# IMX8_INTERFACE.net
KiCad netlist of a schematic drawn in Altium Designer
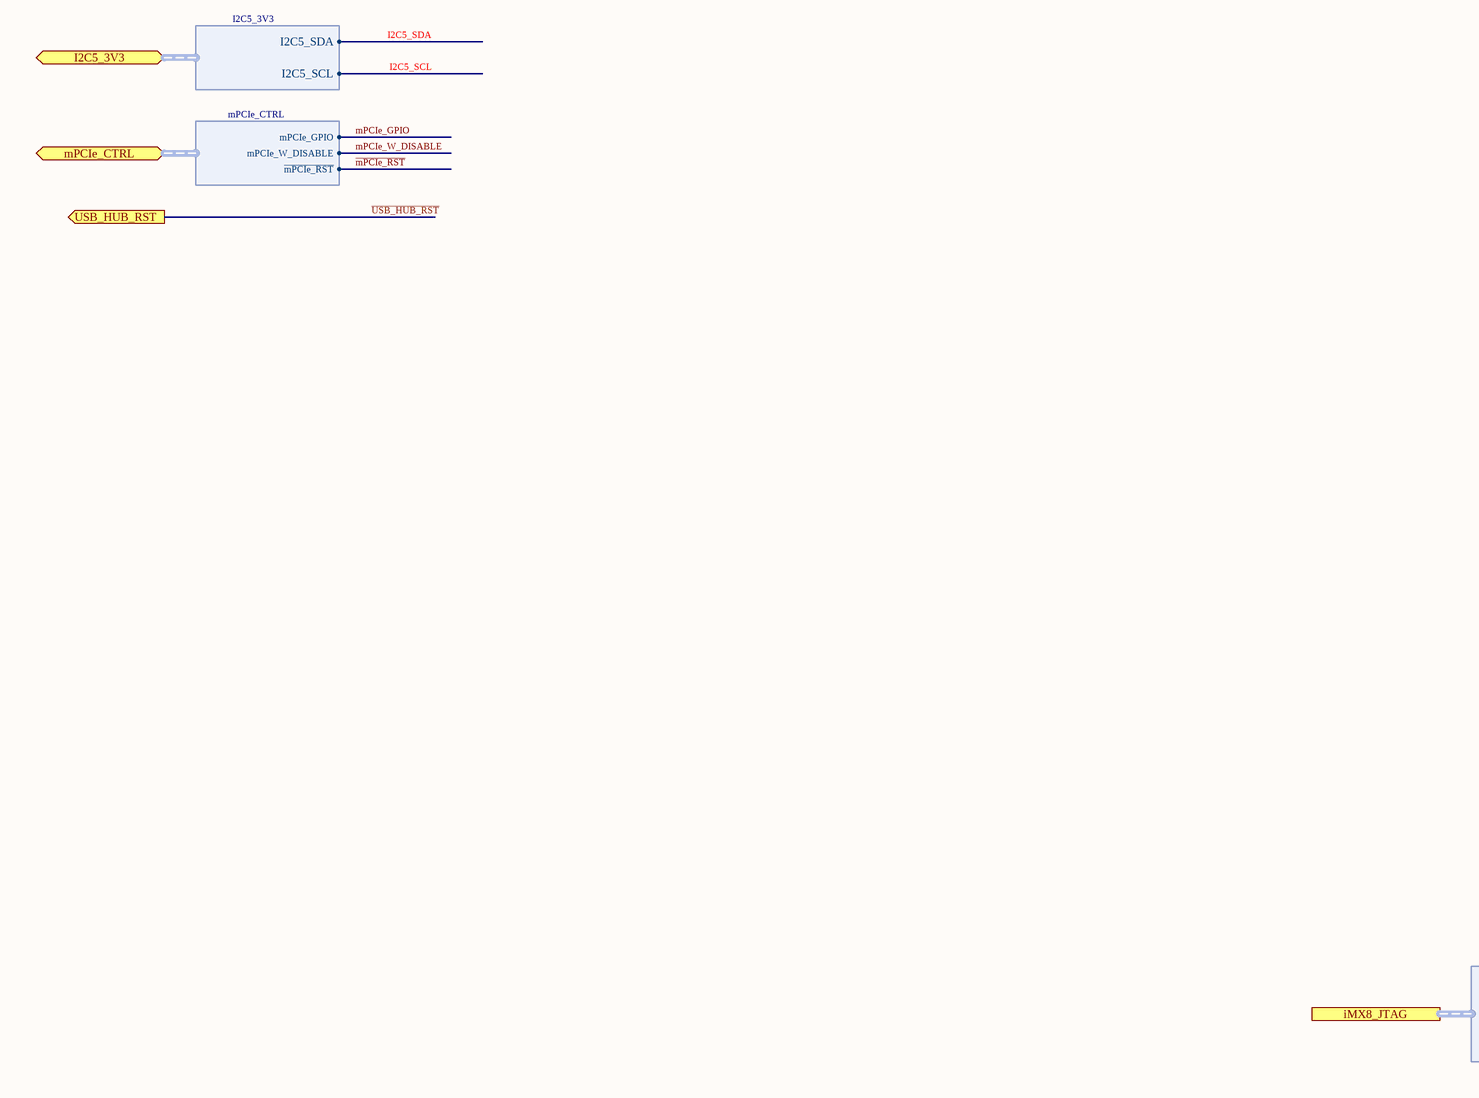
[diagram p0: IMX8_INTERFACE.SchDoc, bottom left]
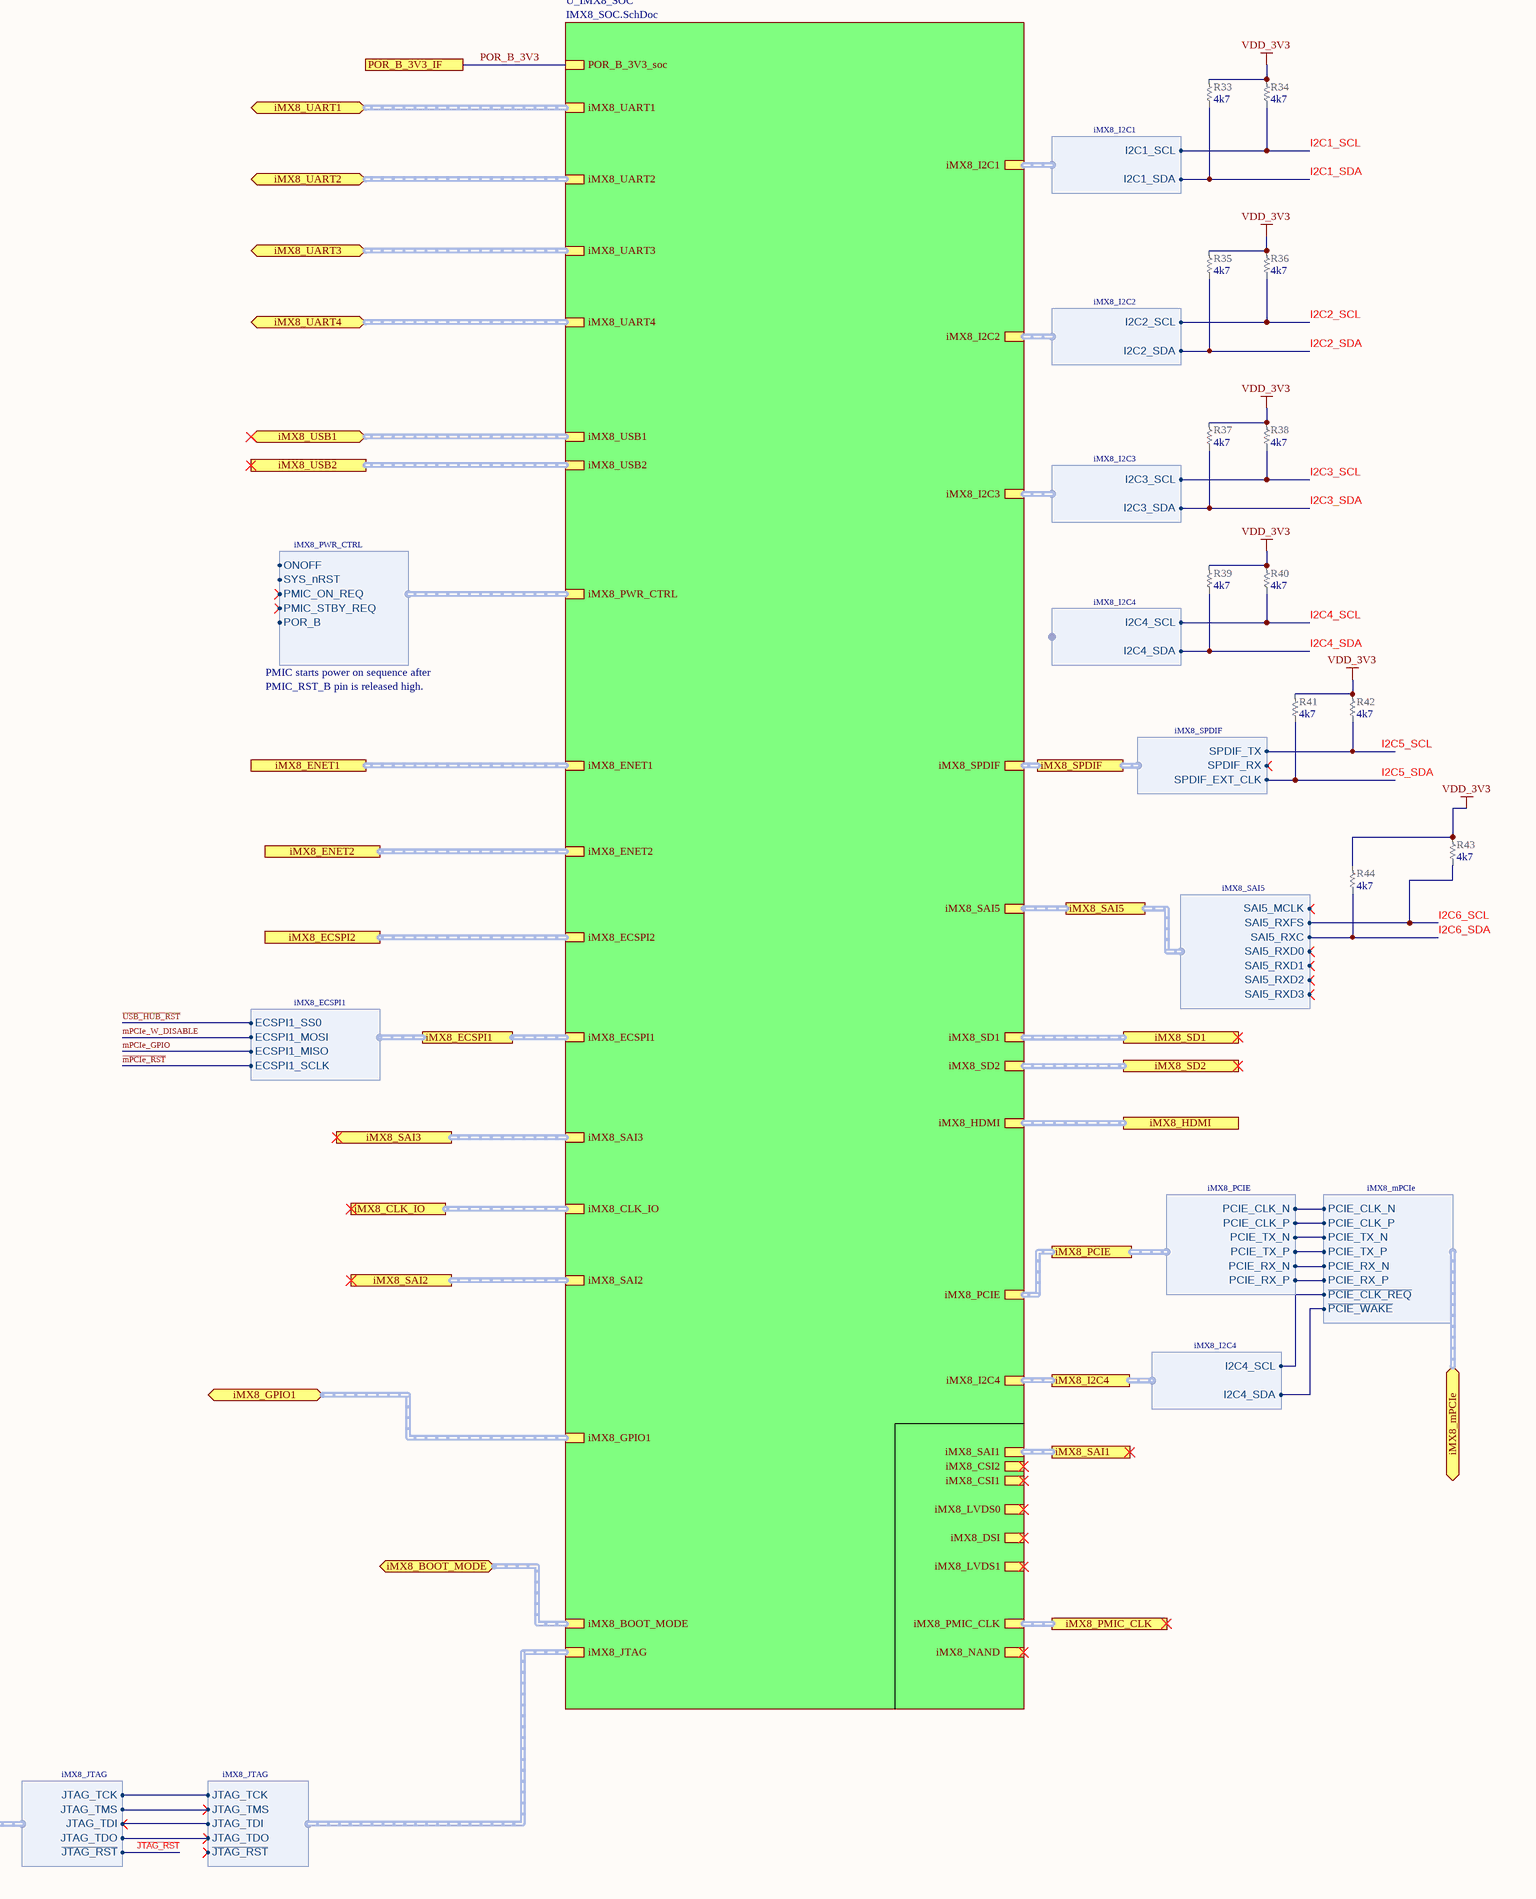
[diagram p1: IMX8_INTERFACE.SchDoc, bottom right]

(export (version "E")
  (design (tool "Eeschema 10.0.6"))
  (components
    (comp (ref "R33")
      (value "4k7")
      (footprint "RES_0201_UN1Q")
      (description "RES")
      (fields (field (name "PART NUMBER") "RC0201FR-074K7L") (field (name "MANUFACTURER") "Yageo Group"))
      (libsource (lib "CM5_library") (part "CMP-001-000475-13"))
    )
    (comp (ref "R34")
      (value "4k7")
      (footprint "RES_0201_UN1Q")
      (description "RES")
      (fields (field (name "PART NUMBER") "RC0201FR-074K7L") (field (name "MANUFACTURER") "Yageo Group"))
      (libsource (lib "CM5_library") (part "CMP-001-000475-13"))
    )
    (comp (ref "R35")
      (value "4k7")
      (footprint "RES_0201_UN1Q")
      (description "RES")
      (fields (field (name "PART NUMBER") "RC0201FR-074K7L") (field (name "MANUFACTURER") "Yageo Group"))
      (libsource (lib "CM5_library") (part "CMP-001-000475-13"))
    )
    (comp (ref "R36")
      (value "4k7")
      (footprint "RES_0201_UN1Q")
      (description "RES")
      (fields (field (name "PART NUMBER") "RC0201FR-074K7L") (field (name "MANUFACTURER") "Yageo Group"))
      (libsource (lib "CM5_library") (part "CMP-001-000475-13"))
    )
    (comp (ref "R37")
      (value "4k7")
      (footprint "RES_0201_UN1Q")
      (description "RES")
      (fields (field (name "PART NUMBER") "RC0201FR-074K7L") (field (name "MANUFACTURER") "Yageo Group"))
      (libsource (lib "CM5_library") (part "CMP-001-000475-13"))
    )
    (comp (ref "R38")
      (value "4k7")
      (footprint "RES_0201_UN1Q")
      (description "RES")
      (fields (field (name "PART NUMBER") "RC0201FR-074K7L") (field (name "MANUFACTURER") "Yageo Group"))
      (libsource (lib "CM5_library") (part "CMP-001-000475-13"))
    )
    (comp (ref "R39")
      (value "4k7")
      (footprint "RES_0201_UN1Q")
      (description "RES")
      (fields (field (name "PART NUMBER") "RC0201FR-074K7L") (field (name "MANUFACTURER") "Yageo Group"))
      (libsource (lib "CM5_library") (part "CMP-001-000475-13"))
    )
    (comp (ref "R40")
      (value "4k7")
      (footprint "RES_0201_UN1Q")
      (description "RES")
      (fields (field (name "PART NUMBER") "RC0201FR-074K7L") (field (name "MANUFACTURER") "Yageo Group"))
      (libsource (lib "CM5_library") (part "CMP-001-000475-13"))
    )
    (comp (ref "R41")
      (value "4k7")
      (footprint "RES_0201_UN1Q")
      (description "RES")
      (fields (field (name "PART NUMBER") "RC0201FR-074K7L") (field (name "MANUFACTURER") "Yageo Group"))
      (libsource (lib "CM5_library") (part "CMP-001-000475-13"))
    )
    (comp (ref "R42")
      (value "4k7")
      (footprint "RES_0201_UN1Q")
      (description "RES")
      (fields (field (name "PART NUMBER") "RC0201FR-074K7L") (field (name "MANUFACTURER") "Yageo Group"))
      (libsource (lib "CM5_library") (part "CMP-001-000475-13"))
    )
    (comp (ref "R43")
      (value "4k7")
      (footprint "RES_0201_UN1Q")
      (description "RES")
      (fields (field (name "PART NUMBER") "RC0201FR-074K7L") (field (name "MANUFACTURER") "Yageo Group"))
      (libsource (lib "CM5_library") (part "CMP-001-000475-13"))
    )
    (comp (ref "R44")
      (value "4k7")
      (footprint "RES_0201_UN1Q")
      (description "RES")
      (fields (field (name "PART NUMBER") "RC0201FR-074K7L") (field (name "MANUFACTURER") "Yageo Group"))
      (libsource (lib "CM5_library") (part "CMP-001-000475-13"))
    )
  )
  (nets
    (net (code "33") (name "/I2C1_SCL") (class "Default")
      (node (ref "R34") (pin "1") (pinfunction "1_1") (pintype "passive"))
    )
    (net (code "34") (name "/I2C1_SDA") (class "Default")
      (node (ref "R33") (pin "1") (pinfunction "1_1") (pintype "passive"))
    )
    (net (code "35") (name "/I2C2_SCL") (class "Default")
      (node (ref "R36") (pin "1") (pinfunction "1_1") (pintype "passive"))
    )
    (net (code "36") (name "/I2C2_SDA") (class "Default")
      (node (ref "R35") (pin "1") (pinfunction "1_1") (pintype "passive"))
    )
    (net (code "37") (name "/I2C3_SCL") (class "Default")
      (node (ref "R38") (pin "1") (pinfunction "1_1") (pintype "passive"))
    )
    (net (code "38") (name "/I2C3_SDA") (class "Default")
      (node (ref "R37") (pin "1") (pinfunction "1_1") (pintype "passive"))
    )
    (net (code "39") (name "/I2C4_SCL") (class "Default")
      (node (ref "R40") (pin "1") (pinfunction "1_1") (pintype "passive"))
    )
    (net (code "40") (name "/I2C4_SDA") (class "Default")
      (node (ref "R39") (pin "1") (pinfunction "1_1") (pintype "passive"))
    )
    (net (code "41") (name "/I2C5_SCL") (class "Default")
      (node (ref "R42") (pin "1") (pinfunction "1_1") (pintype "passive"))
    )
    (net (code "42") (name "/I2C5_SDA") (class "Default")
      (node (ref "R41") (pin "1") (pinfunction "1_1") (pintype "passive"))
    )
    (net (code "43") (name "/I2C6_SCL") (class "Default")
      (node (ref "R43") (pin "1") (pinfunction "1_1") (pintype "passive"))
    )
    (net (code "44") (name "/I2C6_SDA") (class "Default")
      (node (ref "R44") (pin "1") (pinfunction "1_1") (pintype "passive"))
    )
    (net (code "90") (name "VDD_3V3") (class "Default")
      (node (ref "R33") (pin "2") (pinfunction "2_2") (pintype "passive"))
      (node (ref "R34") (pin "2") (pinfunction "2_2") (pintype "passive"))
      (node (ref "R35") (pin "2") (pinfunction "2_2") (pintype "passive"))
      (node (ref "R36") (pin "2") (pinfunction "2_2") (pintype "passive"))
      (node (ref "R37") (pin "2") (pinfunction "2_2") (pintype "passive"))
      (node (ref "R38") (pin "2") (pinfunction "2_2") (pintype "passive"))
      (node (ref "R39") (pin "2") (pinfunction "2_2") (pintype "passive"))
      (node (ref "R40") (pin "2") (pinfunction "2_2") (pintype "passive"))
      (node (ref "R41") (pin "2") (pinfunction "2_2") (pintype "passive"))
      (node (ref "R42") (pin "2") (pinfunction "2_2") (pintype "passive"))
      (node (ref "R43") (pin "2") (pinfunction "2_2") (pintype "passive"))
      (node (ref "R44") (pin "2") (pinfunction "2_2") (pintype "passive"))
    )
  )
)
